# usb.net
KiCad netlist of a schematic drawn in Altium Designer
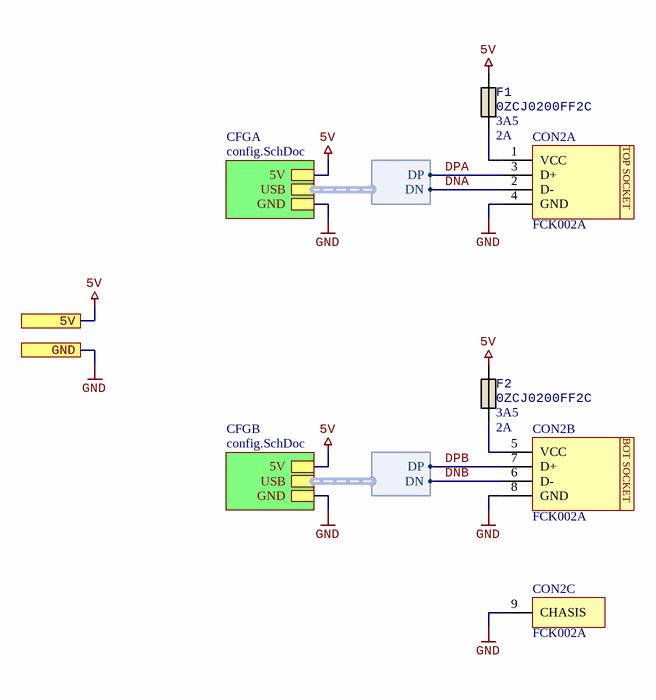
[diagram p0: usb.SchDoc]

(export (version "E")
  (design (tool "Eeschema 10.0.6"))
  (components
    (comp (ref "CON2")
      (value "FCK002A")
      (footprint "USB-A-SOCKET-DOUBLE")
      (description "Dual USB A connector")
      (libsource (lib "connectors") (part "USB-A-Sock-Double"))
    )
    (comp (ref "F1")
      (value "0ZCJ0200FF2C")
      (footprint "FUSE_1206")
      (description "PTC SMD Fuses")
      (fields (field (name "I_TRIP") "3A5") (field (name "I_NOM") "2A"))
      (libsource (lib "misc") (part "PTC"))
    )
    (comp (ref "F2")
      (value "0ZCJ0200FF2C")
      (footprint "FUSE_1206")
      (description "PTC SMD Fuses")
      (fields (field (name "I_TRIP") "3A5") (field (name "I_NOM") "2A"))
      (libsource (lib "misc") (part "PTC"))
    )
  )
  (nets
    (net (code "2") (name "/DNA") (class "Default")
      (node (ref "CON2") (pin "2") (pinfunction "D-_2") (pintype "passive"))
    )
    (net (code "3") (name "/DNB") (class "Default")
      (node (ref "CON2") (pin "6") (pinfunction "D-_6") (pintype "passive"))
    )
    (net (code "4") (name "/DPA") (class "Default")
      (node (ref "CON2") (pin "3") (pinfunction "D+_3") (pintype "passive"))
    )
    (net (code "5") (name "/DPB") (class "Default")
      (node (ref "CON2") (pin "7") (pinfunction "D+_7") (pintype "passive"))
    )
    (net (code "7") (name "5V") (class "Default")
      (node (ref "F1") (pin "2") (pinfunction "2_2") (pintype "passive"))
      (node (ref "F2") (pin "2") (pinfunction "2_2") (pintype "passive"))
    )
    (net (code "8") (name "GND") (class "Default")
      (node (ref "CON2") (pin "4") (pinfunction "GND_4") (pintype "passive"))
      (node (ref "CON2") (pin "8") (pinfunction "GND_8") (pintype "passive"))
      (node (ref "CON2") (pin "9") (pinfunction "CHASIS_9") (pintype "passive"))
    )
    (net (code "9") (name "Net-(CON2A-VCC)") (class "Default")
      (node (ref "CON2") (pin "1") (pinfunction "VCC_1") (pintype "passive"))
      (node (ref "F1") (pin "1") (pinfunction "1_1") (pintype "passive"))
    )
    (net (code "10") (name "Net-(CON2B-VCC)") (class "Default")
      (node (ref "CON2") (pin "5") (pinfunction "VCC_5") (pintype "passive"))
      (node (ref "F2") (pin "1") (pinfunction "1_1") (pintype "passive"))
    )
  )
)
